# TC264MCU.net
KiCad netlist of a schematic drawn in Altium Designer
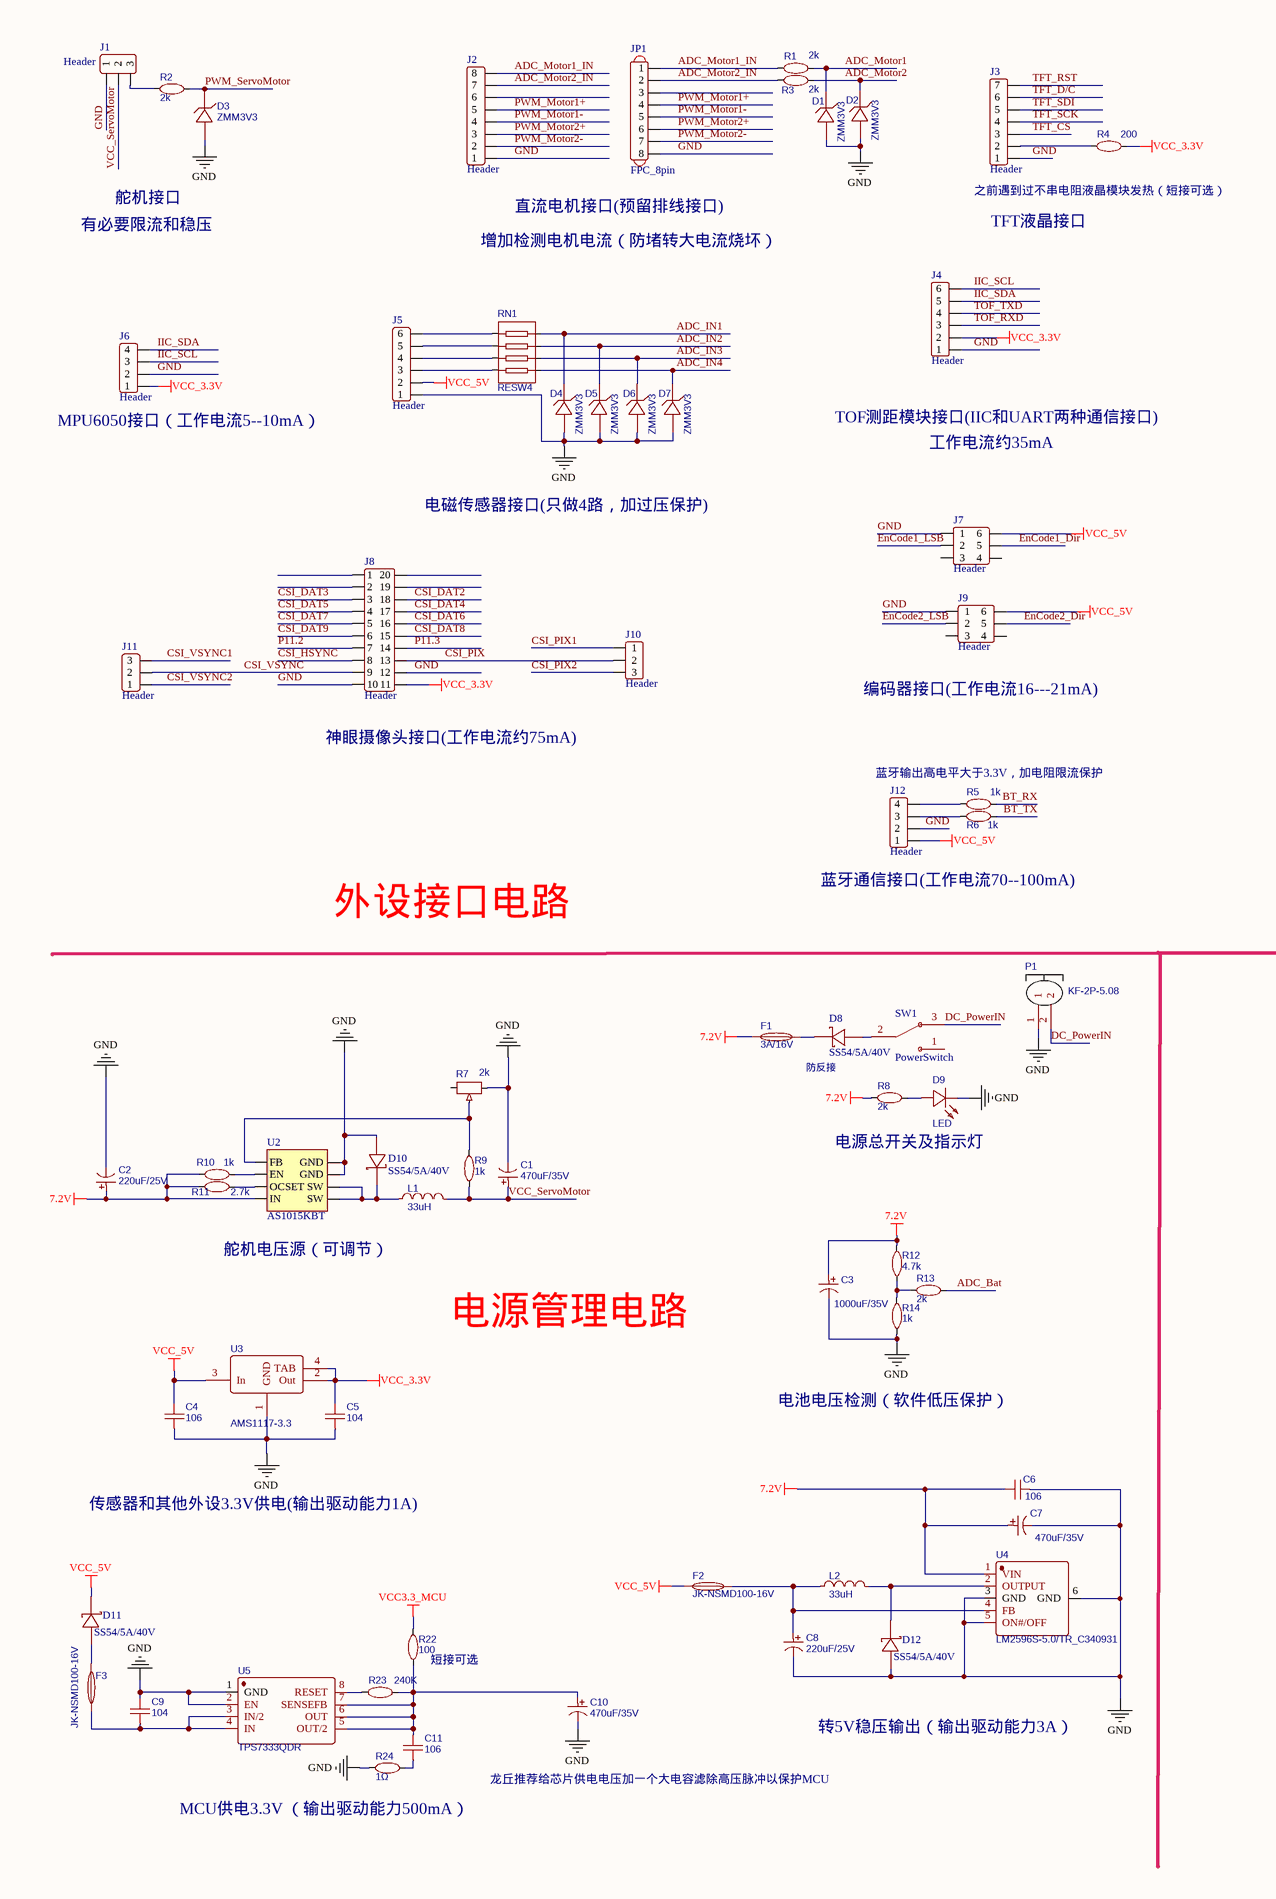
[diagram p0: TC264MCU.SchDoc, left]
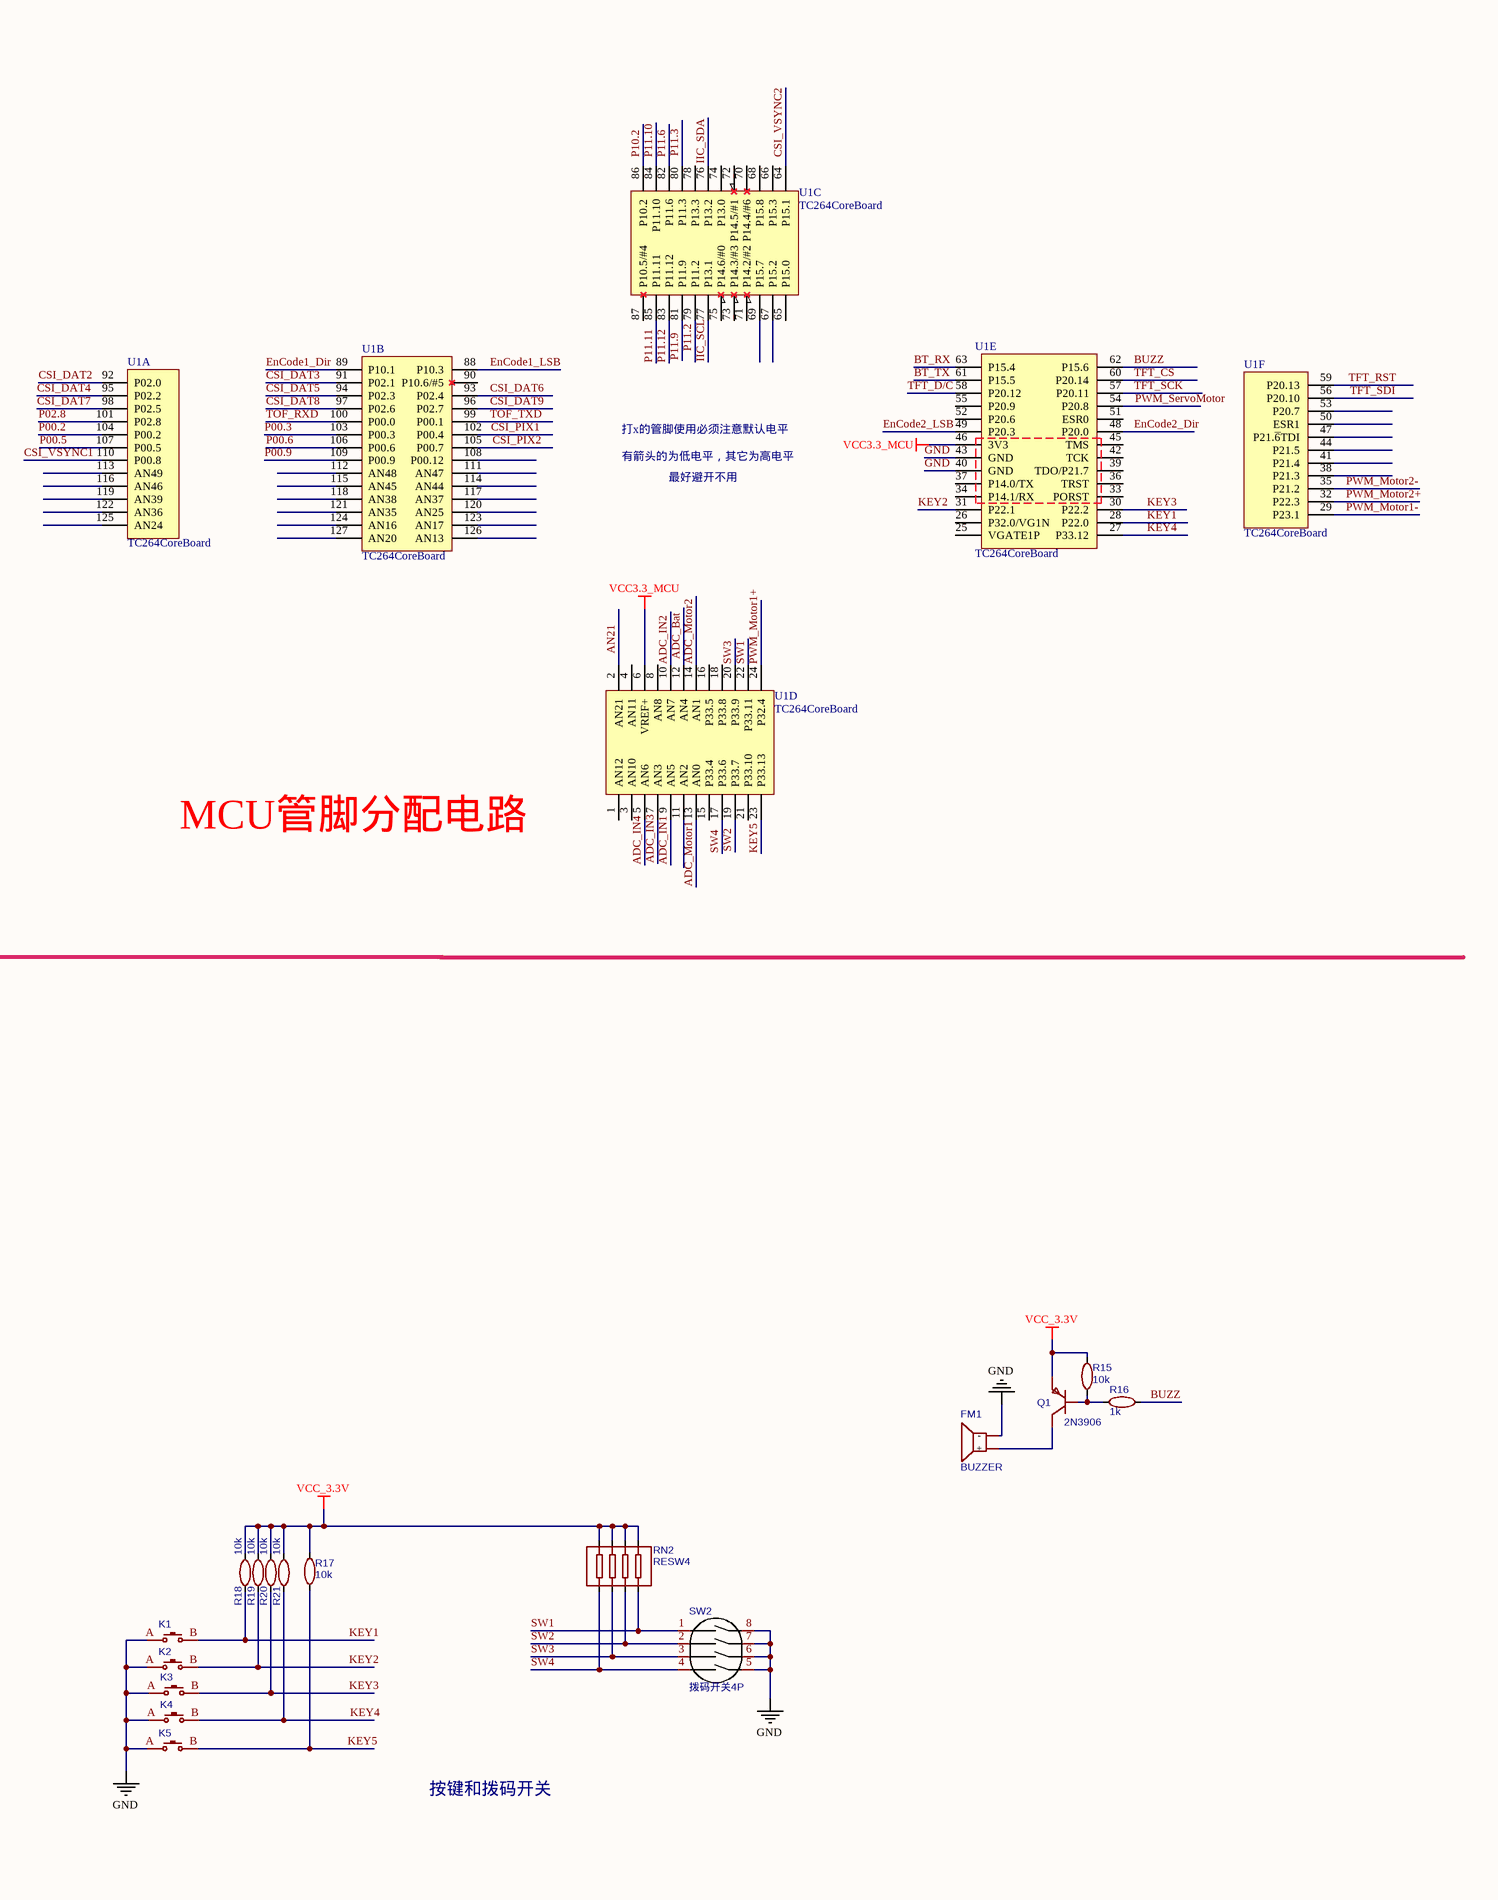
[diagram p1: TC264MCU.SchDoc, right]

(export (version "E")
  (design (tool "Eeschema 10.0.6"))
  (components
    (comp (ref "C1")
      (value "470uF/35V")
      (footprint "CAPE_SMD_G_10.6")
      (description "贴片电解电容")
      (fields
        (field (name "BOM_MANUFACTURER PART") "RVT1C221M0607")
        (field (name "BOM_SUPPLIER PART") "C72496")
      )
      (libsource (lib "LTC_Library1") (part "CAP_E_SMD"))
    )
    (comp (ref "C2")
      (value "220uF/25V")
      (footprint "CAPE_SMD_F_8.4")
      (description "贴片电解电容")
      (fields
        (field (name "BOM_MANUFACTURER PART") "RVT1C221M0607")
        (field (name "BOM_SUPPLIER PART") "C72496")
      )
      (libsource (lib "LTC_Library1") (part "CAP_E_SMD"))
    )
    (comp (ref "C3")
      (value "1000uF/35V")
      (footprint "CAPE_SMD_G_10.6")
      (description "贴片电解电容")
      (fields
        (field (name "BOM_MANUFACTURER PART") "RVT1C221M0607")
        (field (name "BOM_SUPPLIER PART") "C72496")
      )
      (libsource (lib "LTC_Library1") (part "CAP_E_SMD"))
    )
    (comp (ref "C4")
      (value "106")
      (footprint "CAP_0603")
      (fields
        (field (name "BOM_SUPPLIER PART") "C307348")
        (field (name "BOM_MANUFACTURER PART") "CL10B104KB8WPNC")
        (field (name "CONTRIBUTOR") "LCSC")
      )
      (libsource (lib "LTC_Library1") (part "CAP_0603"))
    )
    (comp (ref "C5")
      (value "104")
      (footprint "CAP_0603")
      (fields
        (field (name "BOM_SUPPLIER PART") "C307348")
        (field (name "BOM_MANUFACTURER PART") "CL10B104KB8WPNC")
        (field (name "CONTRIBUTOR") "LCSC")
      )
      (libsource (lib "LTC_Library1") (part "CAP_0603"))
    )
    (comp (ref "C6")
      (value "106")
      (footprint "CAP_0603")
      (fields
        (field (name "BOM_SUPPLIER PART") "C307348")
        (field (name "BOM_MANUFACTURER PART") "CL10B104KB8WPNC")
        (field (name "CONTRIBUTOR") "LCSC")
      )
      (libsource (lib "LTC_Library1") (part "CAP_0603"))
    )
    (comp (ref "C7")
      (value "470uF/35V")
      (footprint "CAPE_SMD_G_10.6")
      (description "贴片电解电容")
      (fields
        (field (name "BOM_MANUFACTURER PART") "RVT1C221M0607")
        (field (name "BOM_SUPPLIER PART") "C72496")
      )
      (libsource (lib "") (part "CAP_E_SMD_1"))
    )
    (comp (ref "C8")
      (value "220uF/25V")
      (footprint "CAPE_SMD_F_8.4")
      (description "贴片电解电容")
      (fields
        (field (name "BOM_MANUFACTURER PART") "RVT1C221M0607")
        (field (name "BOM_SUPPLIER PART") "C72496")
      )
      (libsource (lib "LTC_Library1") (part "CAP_E_SMD"))
    )
    (comp (ref "C9")
      (value "104")
      (footprint "CAP_0603")
      (fields
        (field (name "BOM_SUPPLIER PART") "C307348")
        (field (name "BOM_MANUFACTURER PART") "CL10B104KB8WPNC")
        (field (name "CONTRIBUTOR") "LCSC")
      )
      (libsource (lib "LTC_Library1") (part "CAP_0603"))
    )
    (comp (ref "C10")
      (value "470uF/35V")
      (footprint "CAPE_SMD_G_10.6")
      (description "贴片电解电容")
      (fields
        (field (name "BOM_MANUFACTURER PART") "RVT1C221M0607")
        (field (name "BOM_SUPPLIER PART") "C72496")
      )
      (libsource (lib "LTC_Library1") (part "CAP_E_SMD"))
    )
    (comp (ref "C11")
      (value "106")
      (footprint "CAP_0603")
      (fields
        (field (name "BOM_SUPPLIER PART") "C307348")
        (field (name "BOM_MANUFACTURER PART") "CL10B104KB8WPNC")
        (field (name "CONTRIBUTOR") "LCSC")
      )
      (libsource (lib "LTC_Library1") (part "CAP_0603"))
    )
    (comp (ref "D1")
      (value "ZMM3V3")
      (footprint "LL-34_L3.5-W1.5-RD")
      (fields (field (name "BOM_SUPPLIER PART") "C8056"))
      (libsource (lib "SmartCar_Library") (part "ZMM3V3"))
    )
    (comp (ref "D2")
      (value "ZMM3V3")
      (footprint "LL-34_L3.5-W1.5-RD")
      (fields (field (name "BOM_SUPPLIER PART") "C8056"))
      (libsource (lib "SmartCar_Library") (part "ZMM3V3"))
    )
    (comp (ref "D3")
      (value "ZMM3V3")
      (footprint "LL-34_L3.5-W1.5-RD")
      (fields (field (name "BOM_SUPPLIER PART") "C8056"))
      (libsource (lib "SmartCar_Library") (part "ZMM3V3"))
    )
    (comp (ref "D4")
      (value "ZMM3V3")
      (footprint "LL-34_L3.5-W1.5-RD")
      (fields (field (name "BOM_SUPPLIER PART") "C8056"))
      (libsource (lib "SmartCar_Library") (part "ZMM3V3"))
    )
    (comp (ref "D5")
      (value "ZMM3V3")
      (footprint "LL-34_L3.5-W1.5-RD")
      (fields (field (name "BOM_SUPPLIER PART") "C8056"))
      (libsource (lib "SmartCar_Library") (part "ZMM3V3"))
    )
    (comp (ref "D6")
      (value "ZMM3V3")
      (footprint "LL-34_L3.5-W1.5-RD")
      (fields (field (name "BOM_SUPPLIER PART") "C8056"))
      (libsource (lib "SmartCar_Library") (part "ZMM3V3"))
    )
    (comp (ref "D7")
      (value "ZMM3V3")
      (footprint "LL-34_L3.5-W1.5-RD")
      (fields (field (name "BOM_SUPPLIER PART") "C8056"))
      (libsource (lib "SmartCar_Library") (part "ZMM3V3"))
    )
    (comp (ref "D8")
      (value "SS54/5A/40V")
      (footprint "DO214_SMA")
      (libsource (lib "LTC_Library1") (part "SS54"))
    )
    (comp (ref "D9")
      (value "LED")
      (footprint "LED_0603_B")
      (description "发光LED")
      (fields
        (field (name "BOM_MANUFACTURER PART") "D-G080508G1")
        (field (name "BOM_SUPPLIER PART") "C107402")
        (field (name "CONTRIBUTOR") "LCSC")
      )
      (libsource (lib "LTC_Library1") (part "LED_0603"))
    )
    (comp (ref "D10")
      (value "SS54/5A/40V")
      (footprint "DO214_SMA")
      (libsource (lib "LTC_Library1") (part "SS54"))
    )
    (comp (ref "D11")
      (value "SS54/5A/40V")
      (footprint "DO214_SMA")
      (libsource (lib "LTC_Library1") (part "SS54"))
    )
    (comp (ref "D12")
      (value "SS54/5A/40V")
      (footprint "DO214_SMA")
      (libsource (lib "LTC_Library1") (part "SS54"))
    )
    (comp (ref "F1")
      (value "3A/16V")
      (footprint "F1206")
      (fields
        (field (name "BOM_SUPPLIER PART") "C369161")
        (field (name "BOM_MANUFACTURER PART") "JK-NSMD100-16V")
        (field (name "CONTRIBUTOR") "LCSC")
      )
      (libsource (lib "SmartCar_Library") (part "JK-NSMD100-16V"))
    )
    (comp (ref "F2")
      (value "JK-NSMD100-16V")
      (footprint "F1206")
      (fields (field (name "BOM_SUPPLIER PART") "C369161") (field (name "CONTRIBUTOR") "LCSC"))
      (libsource (lib "SmartCar_Library") (part "JK-NSMD100-16V"))
    )
    (comp (ref "F3")
      (value "JK-NSMD100-16V")
      (footprint "F1206")
      (fields (field (name "BOM_SUPPLIER PART") "C369161") (field (name "CONTRIBUTOR") "LCSC"))
      (libsource (lib "SmartCar_Library") (part "JK-NSMD100-16V"))
    )
    (comp (ref "FM1")
      (value "BUZZER")
      (footprint "BUZZ-12*7.5")
      (description "蜂鸣器")
      (fields (field (name "BOM_MANUFACTURER PART") "TMB12A12") (field (name "BOM_SUPPLIER PART") "C96079"))
      (libsource (lib "LTC_Library1") (part "BUZZER"))
    )
    (comp (ref "J1")
      (value "Header")
      (footprint "Header 2.54X3")
      (libsource (lib "LTC_Library1") (part "Header 2.54_3"))
    )
    (comp (ref "J2")
      (value "Header")
      (footprint "Header 2.54X8")
      (libsource (lib "LTC_Library1") (part "Header 2.54_8"))
    )
    (comp (ref "J3")
      (value "Header")
      (footprint "Header F 2.54X7")
      (libsource (lib "LTC_Library1") (part "Header 2.54_7"))
    )
    (comp (ref "J4")
      (value "Header")
      (footprint "Header 2.54X6")
      (libsource (lib "LTC_Library1") (part "Header 2.54_6"))
    )
    (comp (ref "J5")
      (value "Header")
      (footprint "Header 2.54X6")
      (libsource (lib "LTC_Library1") (part "Header 2.54_6"))
    )
    (comp (ref "J6")
      (value "Header")
      (footprint "Header 2.54X4")
      (libsource (lib "LTC_Library1") (part "Header 2.54_4"))
    )
    (comp (ref "J7")
      (value "Header")
      (footprint "Header 2.54_2X3")
      (libsource (lib "LTC_Library1") (part "Header 2.54_2X3"))
    )
    (comp (ref "J8")
      (value "Header")
      (footprint "Header F 2.54_2x10")
      (libsource (lib "LTC_Library1") (part "Header 2.54_2X10"))
    )
    (comp (ref "J9")
      (value "Header")
      (footprint "Header 2.54_2X3")
      (libsource (lib "LTC_Library1") (part "Header 2.54_2X3"))
    )
    (comp (ref "J10")
      (value "Header")
      (footprint "Header 2.54X3")
      (libsource (lib "LTC_Library1") (part "Header 2.54_3"))
    )
    (comp (ref "J11")
      (value "Header")
      (footprint "Header 2.54X3")
      (libsource (lib "LTC_Library1") (part "Header 2.54_3"))
    )
    (comp (ref "J12")
      (value "Header")
      (footprint "Header F 2.54X4")
      (libsource (lib "LTC_Library1") (part "Header 2.54_4"))
    )
    (comp (ref "JP1")
      (value "FPC_8pin")
      (footprint "FPC_1.0_8P")
      (libsource (lib "LTC_Library1") (part "FPC_8pin"))
    )
    (comp (ref "K1")
      (value "TS-Button_2P")
      (footprint "SW_SMD_6.1*3.7")
      (description "贴片按键 3*6*2.5")
      (fields
        (field (name "BOM_SUPPLIER PART") "C455236")
        (field (name "BOM_MANUFACTURER PART") "TS-1007S-26")
        (field (name "CONTRIBUTOR") "LCSC")
      )
      (libsource (lib "LTC_Library1") (part "TS-Button_2P"))
    )
    (comp (ref "K2")
      (value "TS-Button_2P")
      (footprint "SW_SMD_6.1*3.7")
      (description "贴片按键 3*6*2.5")
      (fields
        (field (name "BOM_SUPPLIER PART") "C455236")
        (field (name "BOM_MANUFACTURER PART") "TS-1007S-26")
        (field (name "CONTRIBUTOR") "LCSC")
      )
      (libsource (lib "LTC_Library1") (part "TS-Button_2P"))
    )
    (comp (ref "K3")
      (value "TS-Button_2P")
      (footprint "SW_SMD_6.1*3.7")
      (description "贴片按键 3*6*2.5")
      (fields
        (field (name "BOM_SUPPLIER PART") "C455236")
        (field (name "BOM_MANUFACTURER PART") "TS-1007S-26")
        (field (name "CONTRIBUTOR") "LCSC")
      )
      (libsource (lib "LTC_Library1") (part "TS-Button_2P"))
    )
    (comp (ref "K4")
      (value "TS-Button_2P")
      (footprint "SW_SMD_6.1*3.7")
      (description "贴片按键 3*6*2.5")
      (fields
        (field (name "BOM_SUPPLIER PART") "C455236")
        (field (name "BOM_MANUFACTURER PART") "TS-1007S-26")
        (field (name "CONTRIBUTOR") "LCSC")
      )
      (libsource (lib "LTC_Library1") (part "TS-Button_2P"))
    )
    (comp (ref "K5")
      (value "TS-Button_2P")
      (footprint "SW_SMD_6.1*3.7")
      (description "贴片按键 3*6*2.5")
      (fields
        (field (name "BOM_SUPPLIER PART") "C455236")
        (field (name "BOM_MANUFACTURER PART") "TS-1007S-26")
        (field (name "CONTRIBUTOR") "LCSC")
      )
      (libsource (lib "LTC_Library1") (part "TS-Button_2P"))
    )
    (comp (ref "L1")
      (value "33uH")
      (footprint "IND-SMD_L8.0-W8.0")
      (fields
        (field (name "BOM_SUPPLIER PART") "C295130")
        (field (name "BOM_MANUFACTURER PART") "NLV25T-330J-EF")
        (field (name "CONTRIBUTOR") "LCSC")
      )
      (libsource (lib "SmartCar_Library") (part "Inductor"))
    )
    (comp (ref "L2")
      (value "33uH")
      (footprint "IND-SMD_L8.0-W8.0")
      (fields
        (field (name "BOM_SUPPLIER PART") "C295130")
        (field (name "BOM_MANUFACTURER PART") "NLV25T-330J-EF")
        (field (name "CONTRIBUTOR") "LCSC")
      )
      (libsource (lib "SmartCar_Library") (part "Inductor"))
    )
    (comp (ref "P1")
      (value "KF-2P-5.08")
      (footprint "KF_2P-5.08")
      (description "端子2P")
      (fields
        (field (name "BOM_MANUFACTURER PART") "WJ500H-5.08-2P")
        (field (name "BOM_SUPPLIER PART") "C8478")
      )
      (libsource (lib "LTC_Library1") (part "KF-2P-5.08"))
    )
    (comp (ref "Q1")
      (value "2N3906")
      (footprint "TO_92A")
      (description "三极管PNP")
      (fields (field (name "BOM_SUPPLIER PART") "C305396") (field (name "CONTRIBUTOR") "LCSC"))
      (libsource (lib "LTC_Library1") (part "2N3906"))
    )
    (comp (ref "R1")
      (value "2k")
      (footprint "RES_0603")
      (fields
        (field (name "BOM_MANUFACTURER PART") "RC0402JR-07100KL")
        (field (name "BOM_SUPPLIER PART") "C106234")
      )
      (libsource (lib "LTC_Library1") (part "RES_0603"))
    )
    (comp (ref "R2")
      (value "2k")
      (footprint "RES_0603")
      (fields
        (field (name "BOM_MANUFACTURER PART") "RC0402JR-07100KL")
        (field (name "BOM_SUPPLIER PART") "C106234")
      )
      (libsource (lib "LTC_Library1") (part "RES_0603"))
    )
    (comp (ref "R3")
      (value "2k")
      (footprint "RES_0603")
      (fields
        (field (name "BOM_MANUFACTURER PART") "RC0402JR-07100KL")
        (field (name "BOM_SUPPLIER PART") "C106234")
      )
      (libsource (lib "LTC_Library1") (part "RES_0603"))
    )
    (comp (ref "R4")
      (value "200")
      (footprint "RES_0603")
      (fields
        (field (name "BOM_MANUFACTURER PART") "RC0402JR-07100KL")
        (field (name "BOM_SUPPLIER PART") "C106234")
      )
      (libsource (lib "LTC_Library1") (part "RES_0603"))
    )
    (comp (ref "R5")
      (value "1k")
      (footprint "RES_0603")
      (fields
        (field (name "BOM_MANUFACTURER PART") "RC0402JR-07100KL")
        (field (name "BOM_SUPPLIER PART") "C106234")
      )
      (libsource (lib "LTC_Library1") (part "RES_0603"))
    )
    (comp (ref "R6")
      (value "1k")
      (footprint "RES_0603")
      (fields
        (field (name "BOM_MANUFACTURER PART") "RC0402JR-07100KL")
        (field (name "BOM_SUPPLIER PART") "C106234")
      )
      (libsource (lib "LTC_Library1") (part "RES_0603"))
    )
    (comp (ref "R7")
      (value "2k")
      (footprint "RES_POT-3296W")
      (description "可调电阻3296W")
      (fields
        (field (name "BOM_SUPPLIER PART") "C118963")
        (field (name "BOM_MANUFACTURER PART") "3296W-1-104")
        (field (name "CONTRIBUTOR") "LCSC")
      )
      (libsource (lib "LTC_Library1") (part "RES_POT-3296W"))
    )
    (comp (ref "R8")
      (value "2k")
      (footprint "RES_0603")
      (fields
        (field (name "BOM_MANUFACTURER PART") "RC0402JR-07100KL")
        (field (name "BOM_SUPPLIER PART") "C106234")
      )
      (libsource (lib "LTC_Library1") (part "RES_0603"))
    )
    (comp (ref "R9")
      (value "1k")
      (footprint "RES_0603")
      (fields
        (field (name "BOM_MANUFACTURER PART") "RC0402JR-07100KL")
        (field (name "BOM_SUPPLIER PART") "C106234")
      )
      (libsource (lib "LTC_Library1") (part "RES_0603"))
    )
    (comp (ref "R10")
      (value "1k")
      (footprint "RES_0603")
      (fields
        (field (name "BOM_MANUFACTURER PART") "RC0402JR-07100KL")
        (field (name "BOM_SUPPLIER PART") "C106234")
      )
      (libsource (lib "LTC_Library1") (part "RES_0603"))
    )
    (comp (ref "R11")
      (value "2.7k")
      (footprint "RES_0603")
      (fields
        (field (name "BOM_MANUFACTURER PART") "RC0402JR-07100KL")
        (field (name "BOM_SUPPLIER PART") "C106234")
      )
      (libsource (lib "LTC_Library1") (part "RES_0603"))
    )
    (comp (ref "R12")
      (value "4.7k")
      (footprint "RES_0603")
      (fields
        (field (name "BOM_MANUFACTURER PART") "RC0402JR-07100KL")
        (field (name "BOM_SUPPLIER PART") "C106234")
      )
      (libsource (lib "LTC_Library1") (part "RES_0603"))
    )
    (comp (ref "R13")
      (value "2k")
      (footprint "RES_0603")
      (fields
        (field (name "BOM_MANUFACTURER PART") "RC0402JR-07100KL")
        (field (name "BOM_SUPPLIER PART") "C106234")
      )
      (libsource (lib "LTC_Library1") (part "RES_0603"))
    )
    (comp (ref "R14")
      (value "1k")
      (footprint "RES_0603")
      (fields
        (field (name "BOM_MANUFACTURER PART") "RC0402JR-07100KL")
        (field (name "BOM_SUPPLIER PART") "C106234")
      )
      (libsource (lib "LTC_Library1") (part "RES_0603"))
    )
    (comp (ref "R15")
      (value "10k")
      (footprint "RES_0603")
      (fields
        (field (name "BOM_MANUFACTURER PART") "RC0402JR-07100KL")
        (field (name "BOM_SUPPLIER PART") "C106234")
      )
      (libsource (lib "LTC_Library1") (part "RES_0603"))
    )
    (comp (ref "R16")
      (value "1k")
      (footprint "RES_0603")
      (fields
        (field (name "BOM_MANUFACTURER PART") "RC0402JR-07100KL")
        (field (name "BOM_SUPPLIER PART") "C106234")
      )
      (libsource (lib "LTC_Library1") (part "RES_0603"))
    )
    (comp (ref "R17")
      (value "10k")
      (footprint "RES_0603")
      (fields
        (field (name "BOM_MANUFACTURER PART") "RC0402JR-07100KL")
        (field (name "BOM_SUPPLIER PART") "C106234")
      )
      (libsource (lib "LTC_Library1") (part "RES_0603"))
    )
    (comp (ref "R18")
      (value "10k")
      (footprint "RES_0603")
      (fields
        (field (name "BOM_MANUFACTURER PART") "RC0402JR-07100KL")
        (field (name "BOM_SUPPLIER PART") "C106234")
      )
      (libsource (lib "LTC_Library1") (part "RES_0603"))
    )
    (comp (ref "R19")
      (value "10k")
      (footprint "RES_0603")
      (fields
        (field (name "BOM_MANUFACTURER PART") "RC0402JR-07100KL")
        (field (name "BOM_SUPPLIER PART") "C106234")
      )
      (libsource (lib "LTC_Library1") (part "RES_0603"))
    )
    (comp (ref "R20")
      (value "10k")
      (footprint "RES_0603")
      (fields
        (field (name "BOM_MANUFACTURER PART") "RC0402JR-07100KL")
        (field (name "BOM_SUPPLIER PART") "C106234")
      )
      (libsource (lib "LTC_Library1") (part "RES_0603"))
    )
    (comp (ref "R21")
      (value "10k")
      (footprint "RES_0603")
      (fields
        (field (name "BOM_MANUFACTURER PART") "RC0402JR-07100KL")
        (field (name "BOM_SUPPLIER PART") "C106234")
      )
      (libsource (lib "LTC_Library1") (part "RES_0603"))
    )
    (comp (ref "R22")
      (value "100")
      (footprint "RES_0603")
      (fields
        (field (name "BOM_MANUFACTURER PART") "RC0402JR-07100KL")
        (field (name "BOM_SUPPLIER PART") "C106234")
      )
      (libsource (lib "LTC_Library1") (part "RES_0603"))
    )
    (comp (ref "R23")
      (value "240K")
      (footprint "RES_0603")
      (fields
        (field (name "BOM_MANUFACTURER PART") "RC0402JR-07100KL")
        (field (name "BOM_SUPPLIER PART") "C106234")
      )
      (libsource (lib "LTC_Library1") (part "RES_0603"))
    )
    (comp (ref "R24")
      (value "1Ω")
      (footprint "RES_0603")
      (fields
        (field (name "BOM_MANUFACTURER PART") "RC0402JR-07100KL")
        (field (name "BOM_SUPPLIER PART") "C106234")
      )
      (libsource (lib "LTC_Library1") (part "RES_0603"))
    )
    (comp (ref "RN1")
      (value "RESW4")
      (footprint "RES-ARRAY-SMD_0603-8P-L3.2-W1.6-BL")
      (fields
        (field (name "BOM_MANUFACTURER PART") "YC164-JR-0710KL")
        (field (name "BOM_SUPPLIER PART") "C107374")
      )
      (libsource (lib "SmartCar_Library") (part "RESW4"))
    )
    (comp (ref "RN2")
      (value "RESW4")
      (footprint "RES-ARRAY-SMD_0603-8P-L3.2-W1.6-BL")
      (fields
        (field (name "BOM_MANUFACTURER PART") "YC164-JR-0710KL")
        (field (name "BOM_SUPPLIER PART") "C107374")
      )
      (libsource (lib "SmartCar_Library") (part "RESW4"))
    )
    (comp (ref "SW1")
      (value "PowerSwitch")
      (footprint "SW-TH_K3-1260D-K1")
      (libsource (lib "SmartCar_Library") (part "PowerSwitch"))
    )
    (comp (ref "SW2")
      (value "拨码开关4P")
      (footprint "MCEMR-04-T")
      (description "DIP_4PX2*2.54")
      (fields
        (field (name "BOM_MANUFACTURER PART") "VDG/S-04HG-R")
        (field (name "BOM_SUPPLIER PART") "C15781")
      )
      (libsource (lib "LTC_Library1") (part "拨码开关4P"))
    )
    (comp (ref "U1")
      (value "TC264CoreBoard")
      (footprint "LQ-TC264-SYSVC-S")
      (libsource (lib "SmartCar_Library") (part "TC264CoreBoard"))
    )
    (comp (ref "U2")
      (value "AS1015KBT")
      (footprint "SOIC-8_150MIL")
      (libsource (lib "SmartCar_Library") (part "AS1015KBT"))
    )
    (comp (ref "U3")
      (value "AMS1117-3.3")
      (footprint "SOT-223_3")
      (fields (field (name "BOM_SUPPLIER PART") "C165482") (field (name "CONTRIBUTOR") "LCSC"))
      (libsource (lib "LTC_Library1") (part "AMS1117-3.3"))
    )
    (comp (ref "U4")
      (value "LM2596S-5.0/TR_C340931")
      (footprint "TO-263_5")
      (fields
        (field (name "BOM_SUPPLIER PART") "C340931")
        (field (name "BOM_MANUFACTURER PART") "LM2596S-5.0/TR")
        (field (name "CONTRIBUTOR") "LCSC")
      )
      (libsource (lib "LTC_Library1") (part "LM2596S-5.0/TR_C340931"))
    )
    (comp (ref "U5")
      (value "TPS7333QDR")
      (footprint "SOIC-8_150MIL")
      (fields (field (name "BOM_SUPPLIER PART") "C23791"))
      (libsource (lib "LTC_Library1") (part "TPS7333QDR"))
    )
  )
  (nets
    (net (code "1") (name "/ADC_Bat") (class "Default")
      (node (ref "R13") (pin "2") (pinfunction "2_2") (pintype "passive"))
      (node (ref "U1") (pin "12") (pinfunction "AN4_12") (pintype "passive"))
    )
    (net (code "2") (name "/ADC_IN1") (class "Default")
      (node (ref "D4") (pin "1") (pinfunction "C_1") (pintype "passive"))
      (node (ref "RN1") (pin "8") (pinfunction "8_8") (pintype "passive"))
      (node (ref "U1") (pin "9") (pinfunction "AN5_9") (pintype "passive"))
    )
    (net (code "3") (name "/ADC_IN2") (class "Default")
      (node (ref "D5") (pin "1") (pinfunction "C_1") (pintype "passive"))
      (node (ref "RN1") (pin "7") (pinfunction "7_7") (pintype "passive"))
      (node (ref "U1") (pin "10") (pinfunction "AN7_10") (pintype "passive"))
    )
    (net (code "4") (name "/ADC_IN3") (class "Default")
      (node (ref "D6") (pin "1") (pinfunction "C_1") (pintype "passive"))
      (node (ref "RN1") (pin "6") (pinfunction "6_6") (pintype "passive"))
      (node (ref "U1") (pin "7") (pinfunction "AN3_7") (pintype "passive"))
    )
    (net (code "5") (name "/ADC_IN4") (class "Default")
      (node (ref "D7") (pin "1") (pinfunction "C_1") (pintype "passive"))
      (node (ref "RN1") (pin "5") (pinfunction "5_5") (pintype "passive"))
      (node (ref "U1") (pin "5") (pinfunction "AN6_5") (pintype "passive"))
    )
    (net (code "6") (name "/ADC_Motor1") (class "Default")
      (node (ref "D1") (pin "1") (pinfunction "C_1") (pintype "passive"))
      (node (ref "R1") (pin "1") (pinfunction "1_1") (pintype "passive"))
      (node (ref "U1") (pin "13") (pinfunction "AN0_13") (pintype "passive"))
    )
    (net (code "7") (name "/ADC_Motor1_IN") (class "Default")
      (node (ref "J2") (pin "8") (pinfunction "8_8") (pintype "passive"))
      (node (ref "JP1") (pin "1") (pinfunction "1_1") (pintype "passive"))
      (node (ref "R1") (pin "2") (pinfunction "2_2") (pintype "passive"))
    )
    (net (code "8") (name "/ADC_Motor2") (class "Default")
      (node (ref "D2") (pin "1") (pinfunction "C_1") (pintype "passive"))
      (node (ref "R3") (pin "1") (pinfunction "1_1") (pintype "passive"))
      (node (ref "U1") (pin "14") (pinfunction "AN1_14") (pintype "passive"))
    )
    (net (code "9") (name "/ADC_Motor2_IN") (class "Default")
      (node (ref "J2") (pin "7") (pinfunction "7_7") (pintype "passive"))
      (node (ref "JP1") (pin "2") (pinfunction "2_2") (pintype "passive"))
      (node (ref "R3") (pin "2") (pinfunction "2_2") (pintype "passive"))
    )
    (net (code "10") (name "/AN21") (class "Default")
      (node (ref "U1") (pin "2") (pinfunction "AN21_2") (pintype "passive"))
    )
    (net (code "11") (name "/BT_RX") (class "Default")
      (node (ref "R5") (pin "1") (pinfunction "1_1") (pintype "passive"))
      (node (ref "U1") (pin "63") (pinfunction "P15.4_63") (pintype "passive"))
    )
    (net (code "12") (name "/BT_TX") (class "Default")
      (node (ref "R6") (pin "1") (pinfunction "1_1") (pintype "passive"))
      (node (ref "U1") (pin "61") (pinfunction "P15.5_61") (pintype "passive"))
    )
    (net (code "13") (name "/BUZZ") (class "Default")
      (node (ref "R16") (pin "1") (pinfunction "1_1") (pintype "passive"))
      (node (ref "U1") (pin "62") (pinfunction "P15.6_62") (pintype "passive"))
    )
    (net (code "14") (name "/CSI_DAT2") (class "Default")
      (node (ref "J8") (pin "18") (pinfunction "18_18") (pintype "passive"))
      (node (ref "U1") (pin "92") (pinfunction "P02.0_92") (pintype "passive"))
    )
    (net (code "15") (name "/CSI_DAT3") (class "Default")
      (node (ref "J8") (pin "3") (pinfunction "3_3") (pintype "passive"))
      (node (ref "U1") (pin "91") (pinfunction "P02.1_91") (pintype "passive"))
    )
    (net (code "16") (name "/CSI_DAT4") (class "Default")
      (node (ref "J8") (pin "17") (pinfunction "17_17") (pintype "passive"))
      (node (ref "U1") (pin "95") (pinfunction "P02.2_95") (pintype "passive"))
    )
    (net (code "17") (name "/CSI_DAT5") (class "Default")
      (node (ref "J8") (pin "4") (pinfunction "4_4") (pintype "passive"))
      (node (ref "U1") (pin "94") (pinfunction "P02.3_94") (pintype "passive"))
    )
    (net (code "18") (name "/CSI_DAT6") (class "Default")
      (node (ref "J8") (pin "16") (pinfunction "16_16") (pintype "passive"))
      (node (ref "U1") (pin "93") (pinfunction "P02.4_93") (pintype "passive"))
    )
    (net (code "19") (name "/CSI_DAT7") (class "Default")
      (node (ref "J8") (pin "5") (pinfunction "5_5") (pintype "passive"))
      (node (ref "U1") (pin "98") (pinfunction "P02.5_98") (pintype "passive"))
    )
    (net (code "20") (name "/CSI_DAT8") (class "Default")
      (node (ref "J8") (pin "15") (pinfunction "15_15") (pintype "passive"))
      (node (ref "U1") (pin "97") (pinfunction "P02.6_97") (pintype "passive"))
    )
    (net (code "21") (name "/CSI_DAT9") (class "Default")
      (node (ref "J8") (pin "6") (pinfunction "6_6") (pintype "passive"))
      (node (ref "U1") (pin "96") (pinfunction "P02.7_96") (pintype "passive"))
    )
    (net (code "22") (name "/CSI_HSYNC") (class "Default")
      (node (ref "J8") (pin "8") (pinfunction "8_8") (pintype "passive"))
    )
    (net (code "23") (name "/CSI_PIX") (class "Default")
      (node (ref "J10") (pin "2") (pinfunction "2_2") (pintype "passive"))
      (node (ref "J8") (pin "13") (pinfunction "13_13") (pintype "passive"))
    )
    (net (code "24") (name "/CSI_PIX1") (class "Default")
      (node (ref "J10") (pin "1") (pinfunction "1_1") (pintype "passive"))
      (node (ref "U1") (pin "102") (pinfunction "P00.4_102") (pintype "passive"))
    )
    (net (code "25") (name "/CSI_PIX2") (class "Default")
      (node (ref "J10") (pin "3") (pinfunction "3_3") (pintype "passive"))
      (node (ref "U1") (pin "105") (pinfunction "P00.7_105") (pintype "passive"))
    )
    (net (code "26") (name "/CSI_VSYNC") (class "Default")
      (node (ref "J11") (pin "2") (pinfunction "2_2") (pintype "passive"))
      (node (ref "J8") (pin "9") (pinfunction "9_9") (pintype "passive"))
    )
    (net (code "27") (name "/CSI_VSYNC1") (class "Default")
      (node (ref "J11") (pin "3") (pinfunction "3_3") (pintype "passive"))
      (node (ref "U1") (pin "110") (pinfunction "P00.8_110") (pintype "passive"))
    )
    (net (code "28") (name "/CSI_VSYNC2") (class "Default")
      (node (ref "J11") (pin "1") (pinfunction "1_1") (pintype "passive"))
      (node (ref "U1") (pin "64") (pinfunction "P15.1_64") (pintype "passive"))
    )
    (net (code "29") (name "/DC_PowerIN") (class "Default")
      (node (ref "P1") (pin "2") (pinfunction "2_2") (pintype "passive"))
      (node (ref "SW1") (pin "3") (pinfunction "NC_3") (pintype "passive"))
    )
    (net (code "30") (name "/EnCode1_Dir") (class "Default")
      (node (ref "J7") (pin "5") (pinfunction "5_5") (pintype "passive"))
      (node (ref "U1") (pin "89") (pinfunction "P10.1_89") (pintype "passive"))
    )
    (net (code "31") (name "/EnCode1_LSB") (class "Default")
      (node (ref "J7") (pin "2") (pinfunction "2_2") (pintype "passive"))
      (node (ref "U1") (pin "88") (pinfunction "P10.3_88") (pintype "passive"))
    )
    (net (code "32") (name "/EnCode2_Dir") (class "Default")
      (node (ref "J9") (pin "5") (pinfunction "5_5") (pintype "passive"))
      (node (ref "U1") (pin "48") (pinfunction "P20.0_48") (pintype "passive"))
    )
    (net (code "33") (name "/EnCode2_LSB") (class "Default")
      (node (ref "J9") (pin "2") (pinfunction "2_2") (pintype "passive"))
      (node (ref "U1") (pin "49") (pinfunction "P20.3_49") (pintype "passive"))
    )
    (net (code "34") (name "/IIC_SCL") (class "Default")
      (node (ref "J4") (pin "6") (pinfunction "6_6") (pintype "passive"))
      (node (ref "J6") (pin "3") (pinfunction "3_3") (pintype "passive"))
      (node (ref "U1") (pin "77") (pinfunction "P13.1_77") (pintype "passive"))
    )
    (net (code "35") (name "/IIC_SDA") (class "Default")
      (node (ref "J4") (pin "5") (pinfunction "5_5") (pintype "passive"))
      (node (ref "J6") (pin "4") (pinfunction "4_4") (pintype "passive"))
      (node (ref "U1") (pin "76") (pinfunction "P13.2_76") (pintype "passive"))
    )
    (net (code "36") (name "/KEY1") (class "Default")
      (node (ref "K1") (pin "B") (pinfunction "B_B") (pintype "passive"))
      (node (ref "R18") (pin "1") (pinfunction "1_1") (pintype "passive"))
      (node (ref "U1") (pin "28") (pinfunction "P22.0_28") (pintype "passive"))
    )
    (net (code "37") (name "/KEY2") (class "Default")
      (node (ref "K2") (pin "B") (pinfunction "B_B") (pintype "passive"))
      (node (ref "R19") (pin "1") (pinfunction "1_1") (pintype "passive"))
      (node (ref "U1") (pin "31") (pinfunction "P22.1_31") (pintype "passive"))
    )
    (net (code "38") (name "/KEY3") (class "Default")
      (node (ref "K3") (pin "B") (pinfunction "B_B") (pintype "passive"))
      (node (ref "R20") (pin "1") (pinfunction "1_1") (pintype "passive"))
      (node (ref "U1") (pin "30") (pinfunction "P22.2_30") (pintype "passive"))
    )
    (net (code "39") (name "/KEY4") (class "Default")
      (node (ref "K4") (pin "B") (pinfunction "B_B") (pintype "passive"))
      (node (ref "R21") (pin "1") (pinfunction "1_1") (pintype "passive"))
      (node (ref "U1") (pin "27") (pinfunction "P33.12_27") (pintype "passive"))
    )
    (net (code "40") (name "/KEY5") (class "Default")
      (node (ref "K5") (pin "B") (pinfunction "B_B") (pintype "passive"))
      (node (ref "R17") (pin "1") (pinfunction "1_1") (pintype "passive"))
      (node (ref "U1") (pin "23") (pinfunction "P33.13_23") (pintype "passive"))
    )
    (net (code "41") (name "/P00.2") (class "Default")
      (node (ref "U1") (pin "104") (pinfunction "P00.2_104") (pintype "passive"))
    )
    (net (code "42") (name "/P00.3") (class "Default")
      (node (ref "U1") (pin "103") (pinfunction "P00.3_103") (pintype "passive"))
    )
    (net (code "43") (name "/P00.5") (class "Default")
      (node (ref "U1") (pin "107") (pinfunction "P00.5_107") (pintype "passive"))
    )
    (net (code "44") (name "/P00.6") (class "Default")
      (node (ref "U1") (pin "106") (pinfunction "P00.6_106") (pintype "passive"))
    )
    (net (code "45") (name "/P00.9") (class "Default")
      (node (ref "U1") (pin "109") (pinfunction "P00.9_109") (pintype "passive"))
    )
    (net (code "46") (name "/P02.8") (class "Default")
      (node (ref "U1") (pin "101") (pinfunction "P02.8_101") (pintype "passive"))
    )
    (net (code "47") (name "/P10.2") (class "Default")
      (node (ref "U1") (pin "86") (pinfunction "P10.2_86") (pintype "passive"))
    )
    (net (code "48") (name "/P11.2") (class "Default")
      (node (ref "J8") (pin "7") (pinfunction "7_7") (pintype "passive"))
      (node (ref "U1") (pin "79") (pinfunction "P11.2_79") (pintype "passive"))
    )
    (net (code "49") (name "/P11.3") (class "Default")
      (node (ref "J8") (pin "14") (pinfunction "14_14") (pintype "passive"))
      (node (ref "U1") (pin "80") (pinfunction "P11.3_80") (pintype "passive"))
    )
    (net (code "50") (name "/P11.6") (class "Default")
      (node (ref "U1") (pin "82") (pinfunction "P11.6_82") (pintype "passive"))
    )
    (net (code "51") (name "/P11.9") (class "Default")
      (node (ref "U1") (pin "81") (pinfunction "P11.9_81") (pintype "passive"))
    )
    (net (code "52") (name "/P11.10") (class "Default")
      (node (ref "U1") (pin "84") (pinfunction "P11.10_84") (pintype "passive"))
    )
    (net (code "53") (name "/P11.11") (class "Default")
      (node (ref "U1") (pin "85") (pinfunction "P11.11_85") (pintype "passive"))
    )
    (net (code "54") (name "/P11.12") (class "Default")
      (node (ref "U1") (pin "83") (pinfunction "P11.12_83") (pintype "passive"))
    )
    (net (code "55") (name "/PWM_Motor1+") (class "Default")
      (node (ref "J2") (pin "5") (pinfunction "5_5") (pintype "passive"))
      (node (ref "JP1") (pin "4") (pinfunction "4_4") (pintype "passive"))
      (node (ref "U1") (pin "24") (pinfunction "P32.4_24") (pintype "passive"))
    )
    (net (code "56") (name "/PWM_Motor1-") (class "Default")
      (node (ref "J2") (pin "4") (pinfunction "4_4") (pintype "passive"))
      (node (ref "JP1") (pin "5") (pinfunction "5_5") (pintype "passive"))
      (node (ref "U1") (pin "29") (pinfunction "P23.1_29") (pintype "passive"))
    )
    (net (code "57") (name "/PWM_Motor2+") (class "Default")
      (node (ref "J2") (pin "3") (pinfunction "3_3") (pintype "passive"))
      (node (ref "JP1") (pin "6") (pinfunction "6_6") (pintype "passive"))
      (node (ref "U1") (pin "32") (pinfunction "P22.3_32") (pintype "passive"))
    )
    (net (code "58") (name "/PWM_Motor2-") (class "Default")
      (node (ref "J2") (pin "2") (pinfunction "2_2") (pintype "passive"))
      (node (ref "JP1") (pin "7") (pinfunction "7_7") (pintype "passive"))
      (node (ref "U1") (pin "35") (pinfunction "P21.2_35") (pintype "passive"))
    )
    (net (code "59") (name "/PWM_ServoMotor") (class "Default")
      (node (ref "D3") (pin "1") (pinfunction "C_1") (pintype "passive"))
      (node (ref "R2") (pin "1") (pinfunction "1_1") (pintype "passive"))
      (node (ref "U1") (pin "54") (pinfunction "P20.8_54") (pintype "passive"))
    )
    (net (code "60") (name "/SW1") (class "Default")
      (node (ref "RN2") (pin "4") (pinfunction "4_4") (pintype "passive"))
      (node (ref "SW2") (pin "1") (pinfunction "1_1") (pintype "passive"))
      (node (ref "U1") (pin "22") (pinfunction "P33.11_22") (pintype "passive"))
    )
    (net (code "61") (name "/SW2") (class "Default")
      (node (ref "RN2") (pin "3") (pinfunction "3_3") (pintype "passive"))
      (node (ref "SW2") (pin "2") (pinfunction "2_2") (pintype "passive"))
      (node (ref "U1") (pin "19") (pinfunction "P33.7_19") (pintype "passive"))
    )
    (net (code "62") (name "/SW3") (class "Default")
      (node (ref "RN2") (pin "2") (pinfunction "2_2") (pintype "passive"))
      (node (ref "SW2") (pin "3") (pinfunction "3_3") (pintype "passive"))
      (node (ref "U1") (pin "20") (pinfunction "P33.9_20") (pintype "passive"))
    )
    (net (code "63") (name "/SW4") (class "Default")
      (node (ref "RN2") (pin "1") (pinfunction "1_1") (pintype "passive"))
      (node (ref "SW2") (pin "4") (pinfunction "4_4") (pintype "passive"))
      (node (ref "U1") (pin "17") (pinfunction "P33.6_17") (pintype "passive"))
    )
    (net (code "64") (name "/TFT_CS") (class "Default")
      (node (ref "J3") (pin "3") (pinfunction "3_3") (pintype "passive"))
      (node (ref "U1") (pin "60") (pinfunction "P20.14_60") (pintype "passive"))
    )
    (net (code "65") (name "/TFT_D{slash}C") (class "Default")
      (node (ref "J3") (pin "6") (pinfunction "6_6") (pintype "passive"))
      (node (ref "U1") (pin "58") (pinfunction "P20.12_58") (pintype "passive"))
    )
    (net (code "66") (name "/TFT_RST") (class "Default")
      (node (ref "J3") (pin "7") (pinfunction "7_7") (pintype "passive"))
      (node (ref "U1") (pin "59") (pinfunction "P20.13_59") (pintype "passive"))
    )
    (net (code "67") (name "/TFT_SCK") (class "Default")
      (node (ref "J3") (pin "4") (pinfunction "4_4") (pintype "passive"))
      (node (ref "U1") (pin "57") (pinfunction "P20.11_57") (pintype "passive"))
    )
    (net (code "68") (name "/TFT_SDI") (class "Default")
      (node (ref "J3") (pin "5") (pinfunction "5_5") (pintype "passive"))
      (node (ref "U1") (pin "56") (pinfunction "P20.10_56") (pintype "passive"))
    )
    (net (code "69") (name "/TOF_RXD") (class "Default")
      (node (ref "J4") (pin "3") (pinfunction "3_3") (pintype "passive"))
      (node (ref "U1") (pin "100") (pinfunction "P00.0_100") (pintype "passive"))
    )
    (net (code "70") (name "/TOF_TXD") (class "Default")
      (node (ref "J4") (pin "4") (pinfunction "4_4") (pintype "passive"))
      (node (ref "U1") (pin "99") (pinfunction "P00.1_99") (pintype "passive"))
    )
    (net (code "71") (name "/VCC_ServoMotor") (class "Default")
      (node (ref "C1") (pin "1") (pinfunction "1_1") (pintype "passive"))
      (node (ref "J1") (pin "2") (pinfunction "2_2") (pintype "passive"))
      (node (ref "L1") (pin "2") (pinfunction "2_2") (pintype "passive"))
      (node (ref "R9") (pin "1") (pinfunction "1_1") (pintype "passive"))
    )
    (net (code "72") (name "7.2V") (class "Default")
      (node (ref "C2") (pin "1") (pinfunction "1_1") (pintype "passive"))
      (node (ref "C3") (pin "1") (pinfunction "1_1") (pintype "passive"))
      (node (ref "C6") (pin "1") (pinfunction "1_1") (pintype "passive"))
      (node (ref "C7") (pin "1") (pinfunction "1_1") (pintype "passive"))
      (node (ref "F1") (pin "2") (pinfunction "2_2") (pintype "passive"))
      (node (ref "R10") (pin "1") (pinfunction "1_1") (pintype "passive"))
      (node (ref "R11") (pin "1") (pinfunction "1_1") (pintype "passive"))
      (node (ref "R12") (pin "1") (pinfunction "1_1") (pintype "passive"))
      (node (ref "R8") (pin "2") (pinfunction "2_2") (pintype "passive"))
      (node (ref "U2") (pin "4") (pinfunction "IN_4") (pintype "passive"))
      (node (ref "U4") (pin "1") (pinfunction "VIN_1") (pintype "passive"))
    )
    (net (code "73") (name "GND") (class "Default")
      (node (ref "C1") (pin "2") (pinfunction "2_2") (pintype "passive"))
      (node (ref "C10") (pin "2") (pinfunction "2_2") (pintype "passive"))
      (node (ref "C2") (pin "2") (pinfunction "2_2") (pintype "passive"))
      (node (ref "C3") (pin "2") (pinfunction "2_2") (pintype "passive"))
      (node (ref "C4") (pin "2") (pinfunction "2_2") (pintype "passive"))
      (node (ref "C5") (pin "2") (pinfunction "2_2") (pintype "passive"))
      (node (ref "C6") (pin "2") (pinfunction "2_2") (pintype "passive"))
      (node (ref "C7") (pin "2") (pinfunction "2_2") (pintype "passive"))
      (node (ref "C8") (pin "2") (pinfunction "2_2") (pintype "passive"))
      (node (ref "C9") (pin "1") (pinfunction "1_1") (pintype "passive"))
      (node (ref "D1") (pin "2") (pinfunction "A_2") (pintype "passive"))
      (node (ref "D10") (pin "1") (pinfunction "A_1") (pintype "passive"))
      (node (ref "D12") (pin "1") (pinfunction "A_1") (pintype "passive"))
      (node (ref "D2") (pin "2") (pinfunction "A_2") (pintype "passive"))
      (node (ref "D3") (pin "2") (pinfunction "A_2") (pintype "passive"))
      (node (ref "D4") (pin "2") (pinfunction "A_2") (pintype "passive"))
      (node (ref "D5") (pin "2") (pinfunction "A_2") (pintype "passive"))
      (node (ref "D6") (pin "2") (pinfunction "A_2") (pintype "passive"))
      (node (ref "D7") (pin "2") (pinfunction "A_2") (pintype "passive"))
      (node (ref "D9") (pin "C") (pinfunction "C_C") (pintype "passive"))
      (node (ref "FM1") (pin "2") (pinfunction "－_2") (pintype "passive"))
      (node (ref "J1") (pin "1") (pinfunction "1_1") (pintype "passive"))
      (node (ref "J12") (pin "2") (pinfunction "2_2") (pintype "passive"))
      (node (ref "J2") (pin "1") (pinfunction "1_1") (pintype "passive"))
      (node (ref "J3") (pin "1") (pinfunction "1_1") (pintype "passive"))
      (node (ref "J4") (pin "1") (pinfunction "1_1") (pintype "passive"))
      (node (ref "J5") (pin "1") (pinfunction "1_1") (pintype "passive"))
      (node (ref "J6") (pin "2") (pinfunction "2_2") (pintype "passive"))
      (node (ref "J7") (pin "1") (pinfunction "1_1") (pintype "passive"))
      (node (ref "J8") (pin "10") (pinfunction "10_10") (pintype "passive"))
      (node (ref "J8") (pin "12") (pinfunction "12_12") (pintype "passive"))
      (node (ref "J9") (pin "1") (pinfunction "1_1") (pintype "passive"))
      (node (ref "JP1") (pin "8") (pinfunction "8_8") (pintype "passive"))
      (node (ref "K1") (pin "A") (pinfunction "A_A") (pintype "passive"))
      (node (ref "K2") (pin "A") (pinfunction "A_A") (pintype "passive"))
      (node (ref "K3") (pin "A") (pinfunction "A_A") (pintype "passive"))
      (node (ref "K4") (pin "A") (pinfunction "A_A") (pintype "passive"))
      (node (ref "K5") (pin "A") (pinfunction "A_A") (pintype "passive"))
      (node (ref "P1") (pin "1") (pinfunction "1_1") (pintype "passive"))
      (node (ref "R14") (pin "2") (pinfunction "2_2") (pintype "passive"))
      (node (ref "R24") (pin "1") (pinfunction "1_1") (pintype "passive"))
      (node (ref "R7") (pin "1") (pinfunction "1_1") (pintype "passive"))
      (node (ref "SW2") (pin "5") (pinfunction "5_5") (pintype "passive"))
      (node (ref "SW2") (pin "6") (pinfunction "6_6") (pintype "passive"))
      (node (ref "SW2") (pin "7") (pinfunction "7_7") (pintype "passive"))
      (node (ref "SW2") (pin "8") (pinfunction "8_8") (pintype "passive"))
      (node (ref "U1") (pin "40") (pinfunction "GND_40") (pintype "passive"))
      (node (ref "U1") (pin "43") (pinfunction "GND_43") (pintype "passive"))
      (node (ref "U2") (pin "7") (pinfunction "GND_7") (pintype "passive"))
      (node (ref "U2") (pin "8") (pinfunction "GND_8") (pintype "passive"))
      (node (ref "U3") (pin "1") (pinfunction "GND_1") (pintype "passive"))
      (node (ref "U4") (pin "3") (pinfunction "GND_3") (pintype "passive"))
      (node (ref "U4") (pin "5") (pinfunction "ON#/OFF_5") (pintype "passive"))
      (node (ref "U4") (pin "6") (pinfunction "GND_6") (pintype "passive"))
      (node (ref "U5") (pin "1") (pinfunction "GND_1") (pintype "passive"))
      (node (ref "U5") (pin "2") (pinfunction "EN_2") (pintype "passive"))
    )
    (net (code "74") (name "Net-(C11-Pad2)") (class "Default")
      (node (ref "C11") (pin "2") (pinfunction "2_2") (pintype "passive"))
      (node (ref "R24") (pin "2") (pinfunction "2_2") (pintype "passive"))
    )
    (net (code "75") (name "Net-(D8-A)") (class "Default")
      (node (ref "D8") (pin "1") (pinfunction "A_1") (pintype "passive"))
      (node (ref "SW1") (pin "2") (pinfunction "C_2") (pintype "passive"))
    )
    (net (code "76") (name "Net-(D8-C)") (class "Default")
      (node (ref "D8") (pin "2") (pinfunction "C_2") (pintype "passive"))
      (node (ref "F1") (pin "1") (pinfunction "1_1") (pintype "passive"))
    )
    (net (code "77") (name "Net-(D9-PadA)") (class "Default")
      (node (ref "D9") (pin "A") (pinfunction "A_A") (pintype "passive"))
      (node (ref "R8") (pin "1") (pinfunction "1_1") (pintype "passive"))
    )
    (net (code "78") (name "Net-(D10-C)") (class "Default")
      (node (ref "D10") (pin "2") (pinfunction "C_2") (pintype "passive"))
      (node (ref "L1") (pin "1") (pinfunction "1_1") (pintype "passive"))
      (node (ref "U2") (pin "5") (pinfunction "SW_5") (pintype "passive"))
      (node (ref "U2") (pin "6") (pinfunction "SW_6") (pintype "passive"))
    )
    (net (code "79") (name "Net-(D11-A)") (class "Default")
      (node (ref "D11") (pin "1") (pinfunction "A_1") (pintype "passive"))
      (node (ref "F3") (pin "2") (pinfunction "2_2") (pintype "passive"))
    )
    (net (code "80") (name "Net-(D12-C)") (class "Default")
      (node (ref "D12") (pin "2") (pinfunction "C_2") (pintype "passive"))
      (node (ref "L2") (pin "2") (pinfunction "2_2") (pintype "passive"))
      (node (ref "U4") (pin "2") (pinfunction "OUTPUT_2") (pintype "passive"))
    )
    (net (code "81") (name "Net-(FM1-+)") (class "Default")
      (node (ref "FM1") (pin "1") (pinfunction "+_1") (pintype "passive"))
      (node (ref "Q1") (pin "3") (pinfunction "C_3") (pintype "passive"))
    )
    (net (code "82") (name "Net-(J1-Pad3)") (class "Default")
      (node (ref "J1") (pin "3") (pinfunction "3_3") (pintype "passive"))
      (node (ref "R2") (pin "2") (pinfunction "2_2") (pintype "passive"))
    )
    (net (code "83") (name "Net-(J3-Pad2)") (class "Default")
      (node (ref "J3") (pin "2") (pinfunction "2_2") (pintype "passive"))
      (node (ref "R4") (pin "2") (pinfunction "2_2") (pintype "passive"))
    )
    (net (code "84") (name "Net-(J5-Pad3)") (class "Default")
      (node (ref "J5") (pin "3") (pinfunction "3_3") (pintype "passive"))
      (node (ref "RN1") (pin "4") (pinfunction "4_4") (pintype "passive"))
    )
    (net (code "85") (name "Net-(J5-Pad4)") (class "Default")
      (node (ref "J5") (pin "4") (pinfunction "4_4") (pintype "passive"))
      (node (ref "RN1") (pin "3") (pinfunction "3_3") (pintype "passive"))
    )
    (net (code "86") (name "Net-(J5-Pad5)") (class "Default")
      (node (ref "J5") (pin "5") (pinfunction "5_5") (pintype "passive"))
      (node (ref "RN1") (pin "2") (pinfunction "2_2") (pintype "passive"))
    )
    (net (code "87") (name "Net-(J5-Pad6)") (class "Default")
      (node (ref "J5") (pin "6") (pinfunction "6_6") (pintype "passive"))
      (node (ref "RN1") (pin "1") (pinfunction "1_1") (pintype "passive"))
    )
    (net (code "88") (name "Net-(J12-Pad3)") (class "Default")
      (node (ref "J12") (pin "3") (pinfunction "3_3") (pintype "passive"))
      (node (ref "R6") (pin "2") (pinfunction "2_2") (pintype "passive"))
    )
    (net (code "89") (name "Net-(J12-Pad4)") (class "Default")
      (node (ref "J12") (pin "4") (pinfunction "4_4") (pintype "passive"))
      (node (ref "R5") (pin "2") (pinfunction "2_2") (pintype "passive"))
    )
    (net (code "90") (name "Net-(Q1-B)") (class "Default")
      (node (ref "Q1") (pin "2") (pinfunction "B_2") (pintype "passive"))
      (node (ref "R15") (pin "2") (pinfunction "2_2") (pintype "passive"))
      (node (ref "R16") (pin "2") (pinfunction "2_2") (pintype "passive"))
    )
    (net (code "91") (name "Net-(R12-Pad2)") (class "Default")
      (node (ref "R12") (pin "2") (pinfunction "2_2") (pintype "passive"))
      (node (ref "R13") (pin "1") (pinfunction "1_1") (pintype "passive"))
      (node (ref "R14") (pin "1") (pinfunction "1_1") (pintype "passive"))
    )
    (net (code "92") (name "Net-(U2-EN)") (class "Default")
      (node (ref "R10") (pin "2") (pinfunction "2_2") (pintype "passive"))
      (node (ref "U2") (pin "2") (pinfunction "EN_2") (pintype "passive"))
    )
    (net (code "93") (name "Net-(U2-FB)") (class "Default")
      (node (ref "R7") (pin "2") (pinfunction "2_2") (pintype "passive"))
      (node (ref "R9") (pin "2") (pinfunction "2_2") (pintype "passive"))
      (node (ref "U2") (pin "1") (pinfunction "FB_1") (pintype "passive"))
    )
    (net (code "94") (name "Net-(U2-OCSET)") (class "Default")
      (node (ref "R11") (pin "2") (pinfunction "2_2") (pintype "passive"))
      (node (ref "U2") (pin "3") (pinfunction "OCSET_3") (pintype "passive"))
    )
    (net (code "95") (name "Net-(U4-FB)") (class "Default")
      (node (ref "C8") (pin "1") (pinfunction "1_1") (pintype "passive"))
      (node (ref "F2") (pin "1") (pinfunction "1_1") (pintype "passive"))
      (node (ref "L2") (pin "1") (pinfunction "1_1") (pintype "passive"))
      (node (ref "U4") (pin "4") (pinfunction "FB_4") (pintype "passive"))
    )
    (net (code "96") (name "Net-(U5-IN)") (class "Default")
      (node (ref "C9") (pin "2") (pinfunction "2_2") (pintype "passive"))
      (node (ref "F3") (pin "1") (pinfunction "1_1") (pintype "passive"))
      (node (ref "U5") (pin "3") (pinfunction "IN/2_3") (pintype "passive"))
      (node (ref "U5") (pin "4") (pinfunction "IN_4") (pintype "passive"))
    )
    (net (code "97") (name "Net-(U5-OUT)") (class "Default")
      (node (ref "C10") (pin "1") (pinfunction "1_1") (pintype "passive"))
      (node (ref "C11") (pin "1") (pinfunction "1_1") (pintype "passive"))
      (node (ref "R22") (pin "1") (pinfunction "1_1") (pintype "passive"))
      (node (ref "R23") (pin "2") (pinfunction "2_2") (pintype "passive"))
      (node (ref "U5") (pin "5") (pinfunction "OUT/2_5") (pintype "passive"))
      (node (ref "U5") (pin "6") (pinfunction "OUT_6") (pintype "passive"))
      (node (ref "U5") (pin "7") (pinfunction "SENSEFB_7") (pintype "passive"))
    )
    (net (code "98") (name "Net-(U5-RESET)") (class "Default")
      (node (ref "R23") (pin "1") (pinfunction "1_1") (pintype "passive"))
      (node (ref "U5") (pin "8") (pinfunction "RESET_8") (pintype "passive"))
    )
    (net (code "99") (name "VCC3.3_MCU") (class "Default")
      (node (ref "R22") (pin "2") (pinfunction "2_2") (pintype "passive"))
      (node (ref "U1") (pin "46") (pinfunction "3V3_46") (pintype "passive"))
      (node (ref "U1") (pin "6") (pinfunction "VREF+_6") (pintype "passive"))
    )
    (net (code "100") (name "VCC_3.3V") (class "Default")
      (node (ref "C5") (pin "1") (pinfunction "1_1") (pintype "passive"))
      (node (ref "J4") (pin "2") (pinfunction "2_2") (pintype "passive"))
      (node (ref "J6") (pin "1") (pinfunction "1_1") (pintype "passive"))
      (node (ref "J8") (pin "11") (pinfunction "11_11") (pintype "passive"))
      (node (ref "Q1") (pin "1") (pinfunction "E_1") (pintype "passive"))
      (node (ref "R15") (pin "1") (pinfunction "1_1") (pintype "passive"))
      (node (ref "R17") (pin "2") (pinfunction "2_2") (pintype "passive"))
      (node (ref "R18") (pin "2") (pinfunction "2_2") (pintype "passive"))
      (node (ref "R19") (pin "2") (pinfunction "2_2") (pintype "passive"))
      (node (ref "R20") (pin "2") (pinfunction "2_2") (pintype "passive"))
      (node (ref "R21") (pin "2") (pinfunction "2_2") (pintype "passive"))
      (node (ref "R4") (pin "1") (pinfunction "1_1") (pintype "passive"))
      (node (ref "RN2") (pin "5") (pinfunction "5_5") (pintype "passive"))
      (node (ref "RN2") (pin "6") (pinfunction "6_6") (pintype "passive"))
      (node (ref "RN2") (pin "7") (pinfunction "7_7") (pintype "passive"))
      (node (ref "RN2") (pin "8") (pinfunction "8_8") (pintype "passive"))
      (node (ref "U3") (pin "2") (pinfunction "Out_2") (pintype "passive"))
      (node (ref "U3") (pin "4") (pinfunction "TAB_4") (pintype "passive"))
    )
    (net (code "101") (name "VCC_5V") (class "Default")
      (node (ref "C4") (pin "1") (pinfunction "1_1") (pintype "passive"))
      (node (ref "D11") (pin "2") (pinfunction "C_2") (pintype "passive"))
      (node (ref "F2") (pin "2") (pinfunction "2_2") (pintype "passive"))
      (node (ref "J12") (pin "1") (pinfunction "1_1") (pintype "passive"))
      (node (ref "J5") (pin "2") (pinfunction "2_2") (pintype "passive"))
      (node (ref "J7") (pin "6") (pinfunction "6_6") (pintype "passive"))
      (node (ref "J9") (pin "6") (pinfunction "6_6") (pintype "passive"))
      (node (ref "U3") (pin "3") (pinfunction "In_3") (pintype "passive"))
    )
    (net (code "102") (name "unconnected-(J2-Pad6)") (class "Default")
      (node (ref "J2") (pin "6") (pinfunction "6_6") (pintype "passive"))
    )
    (net (code "103") (name "unconnected-(J7-Pad3)") (class "Default")
      (node (ref "J7") (pin "3") (pinfunction "3_3") (pintype "passive"))
    )
    (net (code "104") (name "unconnected-(J7-Pad4)") (class "Default")
      (node (ref "J7") (pin "4") (pinfunction "4_4") (pintype "passive"))
    )
    (net (code "105") (name "unconnected-(J8-Pad1)") (class "Default")
      (node (ref "J8") (pin "1") (pinfunction "1_1") (pintype "passive"))
    )
    (net (code "106") (name "unconnected-(J8-Pad2)") (class "Default")
      (node (ref "J8") (pin "2") (pinfunction "2_2") (pintype "passive"))
    )
    (net (code "107") (name "unconnected-(J8-Pad19)") (class "Default")
      (node (ref "J8") (pin "19") (pinfunction "19_19") (pintype "passive"))
    )
    (net (code "108") (name "unconnected-(J8-Pad20)") (class "Default")
      (node (ref "J8") (pin "20") (pinfunction "20_20") (pintype "passive"))
    )
    (net (code "109") (name "unconnected-(J9-Pad3)") (class "Default")
      (node (ref "J9") (pin "3") (pinfunction "3_3") (pintype "passive"))
    )
    (net (code "110") (name "unconnected-(J9-Pad4)") (class "Default")
      (node (ref "J9") (pin "4") (pinfunction "4_4") (pintype "passive"))
    )
    (net (code "111") (name "unconnected-(JP1-Pad3)") (class "Default")
      (node (ref "JP1") (pin "3") (pinfunction "3_3") (pintype "passive"))
    )
    (net (code "112") (name "unconnected-(R7-Pad3)") (class "Default")
      (node (ref "R7") (pin "3") (pinfunction "3_3") (pintype "passive"))
    )
    (net (code "113") (name "unconnected-(SW1-ON-Pad1)") (class "Default")
      (node (ref "SW1") (pin "1") (pinfunction "ON_1") (pintype "passive"))
    )
    (net (code "114") (name "unconnected-(U1A-AN24-Pad125)") (class "Default")
      (node (ref "U1") (pin "125") (pinfunction "AN24_125") (pintype "passive"))
    )
    (net (code "115") (name "unconnected-(U1A-AN36-Pad122)") (class "Default")
      (node (ref "U1") (pin "122") (pinfunction "AN36_122") (pintype "passive"))
    )
    (net (code "116") (name "unconnected-(U1A-AN39-Pad119)") (class "Default")
      (node (ref "U1") (pin "119") (pinfunction "AN39_119") (pintype "passive"))
    )
    (net (code "117") (name "unconnected-(U1A-AN46-Pad116)") (class "Default")
      (node (ref "U1") (pin "116") (pinfunction "AN46_116") (pintype "passive"))
    )
    (net (code "118") (name "unconnected-(U1A-AN49-Pad113)") (class "Default")
      (node (ref "U1") (pin "113") (pinfunction "AN49_113") (pintype "passive"))
    )
    (net (code "119") (name "unconnected-(U1B-AN13-Pad126)") (class "Default")
      (node (ref "U1") (pin "126") (pinfunction "AN13_126") (pintype "passive"))
    )
    (net (code "120") (name "unconnected-(U1B-AN16-Pad124)") (class "Default")
      (node (ref "U1") (pin "124") (pinfunction "AN16_124") (pintype "passive"))
    )
    (net (code "121") (name "unconnected-(U1B-AN17-Pad123)") (class "Default")
      (node (ref "U1") (pin "123") (pinfunction "AN17_123") (pintype "passive"))
    )
    (net (code "122") (name "unconnected-(U1B-AN20-Pad127)") (class "Default")
      (node (ref "U1") (pin "127") (pinfunction "AN20_127") (pintype "passive"))
    )
    (net (code "123") (name "unconnected-(U1B-AN25-Pad120)") (class "Default")
      (node (ref "U1") (pin "120") (pinfunction "AN25_120") (pintype "passive"))
    )
    (net (code "124") (name "unconnected-(U1B-AN35-Pad121)") (class "Default")
      (node (ref "U1") (pin "121") (pinfunction "AN35_121") (pintype "passive"))
    )
    (net (code "125") (name "unconnected-(U1B-AN37-Pad117)") (class "Default")
      (node (ref "U1") (pin "117") (pinfunction "AN37_117") (pintype "passive"))
    )
    (net (code "126") (name "unconnected-(U1B-AN38-Pad118)") (class "Default")
      (node (ref "U1") (pin "118") (pinfunction "AN38_118") (pintype "passive"))
    )
    (net (code "127") (name "unconnected-(U1B-AN44-Pad114)") (class "Default")
      (node (ref "U1") (pin "114") (pinfunction "AN44_114") (pintype "passive"))
    )
    (net (code "128") (name "unconnected-(U1B-AN45-Pad115)") (class "Default")
      (node (ref "U1") (pin "115") (pinfunction "AN45_115") (pintype "passive"))
    )
    (net (code "129") (name "unconnected-(U1B-AN47-Pad111)") (class "Default")
      (node (ref "U1") (pin "111") (pinfunction "AN47_111") (pintype "passive"))
    )
    (net (code "130") (name "unconnected-(U1B-AN48-Pad112)") (class "Default")
      (node (ref "U1") (pin "112") (pinfunction "AN48_112") (pintype "passive"))
    )
    (net (code "131") (name "unconnected-(U1B-P00.12-Pad108)") (class "Default")
      (node (ref "U1") (pin "108") (pinfunction "P00.12_108") (pintype "passive"))
    )
    (net (code "132") (name "unconnected-(U1B-P10.6{slash}#5-Pad90)") (class "Default")
      (node (ref "U1") (pin "90") (pinfunction "P10.6/#5_90") (pintype "passive"))
    )
    (net (code "133") (name "unconnected-(U1C-P10.5{slash}#4-Pad87)") (class "Default")
      (node (ref "U1") (pin "87") (pinfunction "P10.5/#4_87") (pintype "passive"))
    )
    (net (code "134") (name "unconnected-(U1C-P13.0-Pad74)") (class "Default")
      (node (ref "U1") (pin "74") (pinfunction "P13.0_74") (pintype "passive"))
    )
    (net (code "135") (name "unconnected-(U1C-P13.3-Pad78)") (class "Default")
      (node (ref "U1") (pin "78") (pinfunction "P13.3_78") (pintype "passive"))
    )
    (net (code "136") (name "unconnected-(U1C-P14.2{slash}#2-Pad71)") (class "Default")
      (node (ref "U1") (pin "71") (pinfunction "P14.2/#2_71") (pintype "passive"))
    )
    (net (code "137") (name "unconnected-(U1C-P14.3{slash}#3-Pad73)") (class "Default")
      (node (ref "U1") (pin "73") (pinfunction "P14.3/#3_73") (pintype "passive"))
    )
    (net (code "138") (name "unconnected-(U1C-P14.4{slash}#6-Pad70)") (class "Default")
      (node (ref "U1") (pin "70") (pinfunction "P14.4/#6_70") (pintype "passive"))
    )
    (net (code "139") (name "unconnected-(U1C-P14.5{slash}#1-Pad72)") (class "Default")
      (node (ref "U1") (pin "72") (pinfunction "P14.5/#1_72") (pintype "passive"))
    )
    (net (code "140") (name "unconnected-(U1C-P14.6{slash}#0-Pad75)") (class "Default")
      (node (ref "U1") (pin "75") (pinfunction "P14.6/#0_75") (pintype "passive"))
    )
    (net (code "141") (name "unconnected-(U1C-P15.0-Pad65)") (class "Default")
      (node (ref "U1") (pin "65") (pinfunction "P15.0_65") (pintype "passive"))
    )
    (net (code "142") (name "unconnected-(U1C-P15.2-Pad67)") (class "Default")
      (node (ref "U1") (pin "67") (pinfunction "P15.2_67") (pintype "passive"))
    )
    (net (code "143") (name "unconnected-(U1C-P15.3-Pad66)") (class "Default")
      (node (ref "U1") (pin "66") (pinfunction "P15.3_66") (pintype "passive"))
    )
    (net (code "144") (name "unconnected-(U1C-P15.7-Pad69)") (class "Default")
      (node (ref "U1") (pin "69") (pinfunction "P15.7_69") (pintype "passive"))
    )
    (net (code "145") (name "unconnected-(U1C-P15.8-Pad68)") (class "Default")
      (node (ref "U1") (pin "68") (pinfunction "P15.8_68") (pintype "passive"))
    )
    (net (code "146") (name "unconnected-(U1D-AN2-Pad11)") (class "Default")
      (node (ref "U1") (pin "11") (pinfunction "AN2_11") (pintype "passive"))
    )
    (net (code "147") (name "unconnected-(U1D-AN8-Pad8)") (class "Default")
      (node (ref "U1") (pin "8") (pinfunction "AN8_8") (pintype "passive"))
    )
    (net (code "148") (name "unconnected-(U1D-AN10-Pad3)") (class "Default")
      (node (ref "U1") (pin "3") (pinfunction "AN10_3") (pintype "passive"))
    )
    (net (code "149") (name "unconnected-(U1D-AN11-Pad4)") (class "Default")
      (node (ref "U1") (pin "4") (pinfunction "AN11_4") (pintype "passive"))
    )
    (net (code "150") (name "unconnected-(U1D-AN12-Pad1)") (class "Default")
      (node (ref "U1") (pin "1") (pinfunction "AN12_1") (pintype "passive"))
    )
    (net (code "151") (name "unconnected-(U1D-P33.4-Pad15)") (class "Default")
      (node (ref "U1") (pin "15") (pinfunction "P33.4_15") (pintype "passive"))
    )
    (net (code "152") (name "unconnected-(U1D-P33.5-Pad16)") (class "Default")
      (node (ref "U1") (pin "16") (pinfunction "P33.5_16") (pintype "passive"))
    )
    (net (code "153") (name "unconnected-(U1D-P33.8-Pad18)") (class "Default")
      (node (ref "U1") (pin "18") (pinfunction "P33.8_18") (pintype "passive"))
    )
    (net (code "154") (name "unconnected-(U1D-P33.10-Pad21)") (class "Default")
      (node (ref "U1") (pin "21") (pinfunction "P33.10_21") (pintype "passive"))
    )
    (net (code "155") (name "unconnected-(U1E-ESR0-Pad51)") (class "Default")
      (node (ref "U1") (pin "51") (pinfunction "ESR0_51") (pintype "passive"))
    )
    (net (code "156") (name "unconnected-(U1E-P14.0{slash}TX-Pad37)") (class "Default")
      (node (ref "U1") (pin "37") (pinfunction "P14.0/TX_37") (pintype "passive"))
    )
    (net (code "157") (name "unconnected-(U1E-P14.1{slash}RX-Pad34)") (class "Default")
      (node (ref "U1") (pin "34") (pinfunction "P14.1/RX_34") (pintype "passive"))
    )
    (net (code "158") (name "unconnected-(U1E-P20.6-Pad52)") (class "Default")
      (node (ref "U1") (pin "52") (pinfunction "P20.6_52") (pintype "passive"))
    )
    (net (code "159") (name "unconnected-(U1E-P20.9-Pad55)") (class "Default")
      (node (ref "U1") (pin "55") (pinfunction "P20.9_55") (pintype "passive"))
    )
    (net (code "160") (name "unconnected-(U1E-P32.0{slash}VG1N-Pad26)") (class "Default")
      (node (ref "U1") (pin "26") (pinfunction "P32.0/VG1N_26") (pintype "passive"))
    )
    (net (code "161") (name "unconnected-(U1E-PORST-Pad33)") (class "Default")
      (node (ref "U1") (pin "33") (pinfunction "PORST_33") (pintype "passive"))
    )
    (net (code "162") (name "unconnected-(U1E-TCK-Pad42)") (class "Default")
      (node (ref "U1") (pin "42") (pinfunction "TCK_42") (pintype "passive"))
    )
    (net (code "163") (name "unconnected-(U1E-TDO{slash}P21.7-Pad39)") (class "Default")
      (node (ref "U1") (pin "39") (pinfunction "TDO/P21.7_39") (pintype "passive"))
    )
    (net (code "164") (name "unconnected-(U1E-TMS-Pad45)") (class "Default")
      (node (ref "U1") (pin "45") (pinfunction "TMS_45") (pintype "passive"))
    )
    (net (code "165") (name "unconnected-(U1E-TRST-Pad36)") (class "Default")
      (node (ref "U1") (pin "36") (pinfunction "TRST_36") (pintype "passive"))
    )
    (net (code "166") (name "unconnected-(U1E-VGATE1P-Pad25)") (class "Default")
      (node (ref "U1") (pin "25") (pinfunction "VGATE1P_25") (pintype "passive"))
    )
    (net (code "167") (name "unconnected-(U1F-ESR1-Pad50)") (class "Default")
      (node (ref "U1") (pin "50") (pinfunction "ESR1_50") (pintype "passive"))
    )
    (net (code "168") (name "unconnected-(U1F-P20.7-Pad53)") (class "Default")
      (node (ref "U1") (pin "53") (pinfunction "P20.7_53") (pintype "passive"))
    )
    (net (code "169") (name "unconnected-(U1F-P21.3-Pad38)") (class "Default")
      (node (ref "U1") (pin "38") (pinfunction "P21.3_38") (pintype "passive"))
    )
    (net (code "170") (name "unconnected-(U1F-P21.4-Pad41)") (class "Default")
      (node (ref "U1") (pin "41") (pinfunction "P21.4_41") (pintype "passive"))
    )
    (net (code "171") (name "unconnected-(U1F-P21.5-Pad44)") (class "Default")
      (node (ref "U1") (pin "44") (pinfunction "P21.5_44") (pintype "passive"))
    )
    (net (code "172") (name "unconnected-(U1F-P21.~{6}TDI-Pad47)") (class "Default")
      (node (ref "U1") (pin "47") (pinfunction "P21.~{6}TDI_47") (pintype "passive"))
    )
  )
)
